# Power_for_Master.net
KiCad netlist of a schematic drawn in Altium Designer
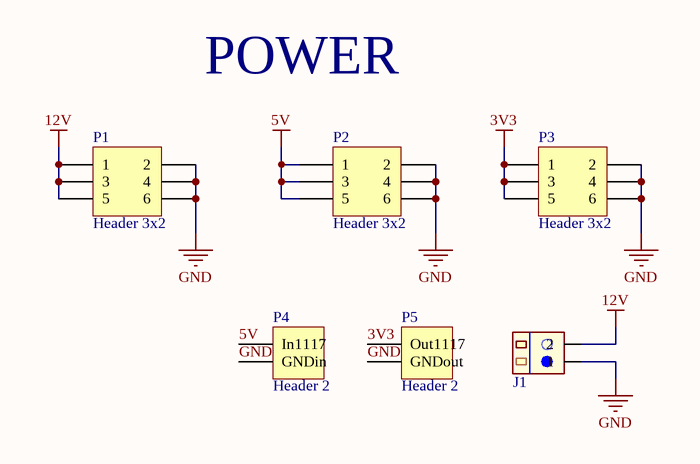
[diagram p0: Power for Master.SchDoc]

(export (version "E")
  (design (tool "Eeschema 10.0.6"))
  (components
    (comp (ref "J1")
      (value "CON.Domino2")
      (footprint "Domino 2M")
      (description "2 pins Domino Header")
      (fields (field (name "PUBLISHER") "Hoang Nguyen"))
      (libsource (lib "THG") (part "CON.Domino2"))
    )
    (comp (ref "P1")
      (value "Header 3x2")
      (footprint "Header 3x2")
      (description "Header, 6-Pin, 2-Row")
      (fields (field (name "PUBLISHER") "Altium Limited"))
      (libsource (lib "THG") (part "Header 3x2"))
    )
    (comp (ref "P2")
      (value "Header 3x2")
      (footprint "Header 3x2")
      (description "Header, 6-Pin, 2-Row")
      (fields (field (name "PUBLISHER") "Altium Limited"))
      (libsource (lib "THG") (part "Header 3x2"))
    )
    (comp (ref "P3")
      (value "Header 3x2")
      (footprint "Header 3x2")
      (description "Header, 6-Pin, 2-Row")
      (fields (field (name "PUBLISHER") "Altium Limited"))
      (libsource (lib "THG") (part "Header 3x2"))
    )
    (comp (ref "P4")
      (value "Header 2")
      (footprint "HDR1X2")
      (description "Header, 2-Pin")
      (fields (field (name "PUBLISHER") "Altium Limited"))
      (libsource (lib "Miscellaneous Connectors") (part "Header 2"))
    )
    (comp (ref "P5")
      (value "Header 2")
      (footprint "HDR1X2")
      (description "Header, 2-Pin")
      (fields (field (name "PUBLISHER") "Altium Limited"))
      (libsource (lib "Miscellaneous Connectors") (part "Header 2"))
    )
  )
  (nets
    (net (code "1") (name "3V3") (class "Default")
      (node (ref "P3") (pin "1") (pinfunction "1_1") (pintype "passive"))
      (node (ref "P3") (pin "3") (pinfunction "3_3") (pintype "passive"))
      (node (ref "P3") (pin "5") (pinfunction "5_5") (pintype "passive"))
      (node (ref "P5") (pin "1") (pinfunction "Out1117_1") (pintype "passive"))
    )
    (net (code "2") (name "5V") (class "Default")
      (node (ref "P2") (pin "1") (pinfunction "1_1") (pintype "passive"))
      (node (ref "P2") (pin "3") (pinfunction "3_3") (pintype "passive"))
      (node (ref "P2") (pin "5") (pinfunction "5_5") (pintype "passive"))
      (node (ref "P4") (pin "1") (pinfunction "Out1117_1") (pintype "passive"))
    )
    (net (code "3") (name "12V") (class "Default")
      (node (ref "J1") (pin "2") (pinfunction "2_2") (pintype "passive"))
      (node (ref "P1") (pin "1") (pinfunction "1_1") (pintype "passive"))
      (node (ref "P1") (pin "3") (pinfunction "3_3") (pintype "passive"))
      (node (ref "P1") (pin "5") (pinfunction "5_5") (pintype "passive"))
    )
    (net (code "4") (name "GND") (class "Default")
      (node (ref "J1") (pin "1") (pinfunction "1_1") (pintype "passive"))
      (node (ref "P1") (pin "2") (pinfunction "2_2") (pintype "passive"))
      (node (ref "P1") (pin "4") (pinfunction "4_4") (pintype "passive"))
      (node (ref "P1") (pin "6") (pinfunction "6_6") (pintype "passive"))
      (node (ref "P2") (pin "2") (pinfunction "2_2") (pintype "passive"))
      (node (ref "P2") (pin "4") (pinfunction "4_4") (pintype "passive"))
      (node (ref "P2") (pin "6") (pinfunction "6_6") (pintype "passive"))
      (node (ref "P3") (pin "2") (pinfunction "2_2") (pintype "passive"))
      (node (ref "P3") (pin "4") (pinfunction "4_4") (pintype "passive"))
      (node (ref "P3") (pin "6") (pinfunction "6_6") (pintype "passive"))
      (node (ref "P4") (pin "2") (pinfunction "GNDout_2") (pintype "passive"))
      (node (ref "P5") (pin "2") (pinfunction "GNDout_2") (pintype "passive"))
    )
  )
)
